# MCU.net
KiCad netlist of a schematic drawn in Altium Designer
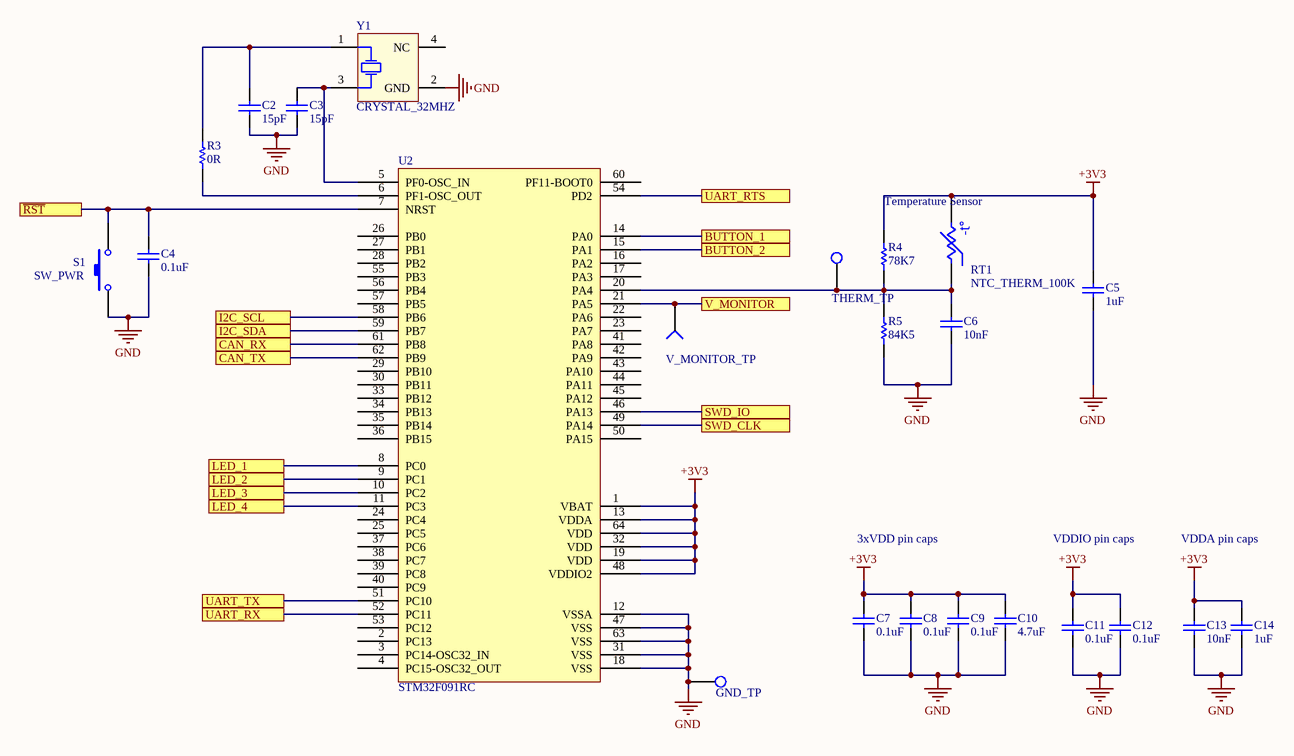
[diagram p0: MCU.SchDoc]

(export (version "E")
  (design (tool "Eeschema 10.0.6"))
  (components
    (comp (ref "C2")
      (value "15pF")
      (footprint "CAPC0603(1608)55_N")
      (description "CAP CER 15PF 250V NPO 0603")
      (fields (field (name "PART NUMBER") "AC0603JRNPOYBN150") (field (name "MANUFACTURER") "Yageo"))
      (libsource (lib "UWRT_Schematic_Library_2019") (part "CAP_15pF_0603"))
    )
    (comp (ref "C3")
      (value "15pF")
      (footprint "CAPC0603(1608)55_N")
      (description "CAP CER 15PF 250V NPO 0603")
      (fields (field (name "PART NUMBER") "AC0603JRNPOYBN150") (field (name "MANUFACTURER") "Yageo"))
      (libsource (lib "UWRT_Schematic_Library_2019") (part "CAP_15pF_0603"))
    )
    (comp (ref "C4")
      (value "0.1uF")
      (footprint "CAPC0603(1608)55_N")
      (description "CAP CER 0.1UF 16V X7R 0603")
      (fields (field (name "PART NUMBER") "CC0603KRX7R7BB104") (field (name "MANUFACTURER") "Yageo"))
      (libsource (lib "UWRT_Schematic_Library_2019") (part "CAP_0.1uF_16V_0603"))
    )
    (comp (ref "C5")
      (value "1uF")
      (footprint "CAPC0603(1608)55_N")
      (description "CAP CER 1UF 16V Y5V 0603")
      (fields (field (name "PART NUMBER") "CC0603ZRY5V7BB105") (field (name "MANUFACTURER") "Yageo"))
      (libsource (lib "UWRT_Schematic_Library_2019") (part "CAP_1uF_16V_0603"))
    )
    (comp (ref "C6")
      (value "10nF")
      (footprint "CAPC0603(1608)55_N")
      (description "CAP CER 10000PF 16V X7R 0603")
      (fields (field (name "PART NUMBER") "CC0603KRX7R7BB103") (field (name "MANUFACTURER") "Yageo"))
      (libsource (lib "UWRT_Schematic_Library_2019") (part "CAP_10nF_0603"))
    )
    (comp (ref "C7")
      (value "0.1uF")
      (footprint "CAPC0603(1608)55_N")
      (description "CAP CER 0.1UF 16V X7R 0603")
      (fields (field (name "PART NUMBER") "CC0603KRX7R7BB104") (field (name "MANUFACTURER") "Yageo"))
      (libsource (lib "UWRT_Schematic_Library_2019") (part "CAP_0.1uF_16V_0603"))
    )
    (comp (ref "C8")
      (value "0.1uF")
      (footprint "CAPC0603(1608)55_N")
      (description "CAP CER 0.1UF 16V X7R 0603")
      (fields (field (name "PART NUMBER") "CC0603KRX7R7BB104") (field (name "MANUFACTURER") "Yageo"))
      (libsource (lib "UWRT_Schematic_Library_2019") (part "CAP_0.1uF_16V_0603"))
    )
    (comp (ref "C9")
      (value "0.1uF")
      (footprint "CAPC0603(1608)55_N")
      (description "CAP CER 0.1UF 16V X7R 0603")
      (fields (field (name "PART NUMBER") "CC0603KRX7R7BB104") (field (name "MANUFACTURER") "Yageo"))
      (libsource (lib "UWRT_Schematic_Library_2019") (part "CAP_0.1uF_16V_0603"))
    )
    (comp (ref "C10")
      (value "4.7uF")
      (footprint "CAPC0603(1608)55_N")
      (description "CAP CER 4.7UF 6.3V X5R 0603")
      (fields (field (name "PART NUMBER") "CC0603KRX5R5BB475") (field (name "MANUFACTURER") "Yageo"))
      (libsource (lib "UWRT_Schematic_Library_2019") (part "CAP_4.7uF_0603"))
    )
    (comp (ref "C11")
      (value "0.1uF")
      (footprint "CAPC0603(1608)55_N")
      (description "CAP CER 0.1UF 16V X7R 0603")
      (fields (field (name "PART NUMBER") "CC0603KRX7R7BB104") (field (name "MANUFACTURER") "Yageo"))
      (libsource (lib "UWRT_Schematic_Library_2019") (part "CAP_0.1uF_16V_0603"))
    )
    (comp (ref "C12")
      (value "0.1uF")
      (footprint "CAPC0603(1608)55_N")
      (description "CAP CER 0.1UF 16V X7R 0603")
      (fields (field (name "PART NUMBER") "CC0603KRX7R7BB104") (field (name "MANUFACTURER") "Yageo"))
      (libsource (lib "UWRT_Schematic_Library_2019") (part "CAP_0.1uF_16V_0603"))
    )
    (comp (ref "C13")
      (value "10nF")
      (footprint "CAPC0603(1608)55_N")
      (description "CAP CER 10000PF 16V X7R 0603")
      (fields (field (name "PART NUMBER") "CC0603KRX7R7BB103") (field (name "MANUFACTURER") "Yageo"))
      (libsource (lib "UWRT_Schematic_Library_2019") (part "CAP_10nF_0603"))
    )
    (comp (ref "C14")
      (value "1uF")
      (footprint "CAPC0603(1608)55_N")
      (description "CAP CER 1UF 16V Y5V 0603")
      (fields (field (name "PART NUMBER") "CC0603ZRY5V7BB105") (field (name "MANUFACTURER") "Yageo"))
      (libsource (lib "UWRT_Schematic_Library_2019") (part "CAP_1uF_16V_0603"))
    )
    (comp (ref "R3")
      (value "0R")
      (footprint "RESC0603(1608)_N")
      (description "RES SMD 0 OHM JUMPER 1/10W 0603")
      (fields (field (name "MANUFACTURER") "Yageo") (field (name "Comment") "RES_0R_0603"))
      (libsource (lib "UWRT_Schematic_Library_2019") (part "RES_0R_0603"))
    )
    (comp (ref "R4")
      (value "78K7")
      (footprint "RESC0603(1608)_N")
      (description "RES SMD 78.7K OHM 1% 1/10W 0603")
      (fields (field (name "MANUFACTURER") "Yageo") (field (name "TOLERANCE") "1%"))
      (libsource (lib "UWRT_Schematic_Library_2019") (part "RES_78K7_0603"))
    )
    (comp (ref "R5")
      (value "84K5")
      (footprint "RESC0603(1608)_N")
      (description "RES SMD 84.5K OHM 1% 1/10W 0603")
      (fields (field (name "MANUFACTURER") "Yageo") (field (name "TOLERANCE") "1%"))
      (libsource (lib "UWRT_Schematic_Library_2019") (part "RES_84K5_0603"))
    )
    (comp (ref "RT1")
      (value "NTC_THERM_100K")
      (footprint "RESC0603(1608)_N")
      (description "THERM NTC 100KOHM 4700K 0603")
      (fields (field (name "MPN") "ERT-J1VV104J") (field (name "DIGIKEY PART NUMBER") "P10555CT-ND"))
      (libsource (lib "UWRT_Schematic_Library_2019") (part "NTC_THERM_100K"))
    )
    (comp (ref "S1")
      (value "SW_PWR")
      (footprint "PTS830GM140")
      (description "Power Switch (Red)")
      (fields (field (name "PART NUMBER") "PTS830GM140 SMTR LFS"))
      (libsource (lib "UWRT_Schematic_Library_2019") (part "SW_PWR"))
    )
    (comp (ref "TP3")
      (value "THERM_TP")
      (footprint "TESTPOINT_LOOP")
      (libsource (lib "UWRT_Schematic_Library_2019") (part "TESTPOINT_LOOP"))
    )
    (comp (ref "TP4")
      (value "V_MONITOR_TP")
      (footprint "TESTPOINT")
      (libsource (lib "UWRT_Schematic_Library_2019") (part "TESTPOINT_SMD"))
    )
    (comp (ref "TP5")
      (value "GND_TP")
      (footprint "TESTPOINT_LOOP")
      (libsource (lib "UWRT_Schematic_Library_2019") (part "TESTPOINT_LOOP"))
    )
    (comp (ref "U2")
      (value "STM32F091RC")
      (footprint "UWRT_Footprint_Library_2019:STM_LQFP64_N")
      (fields (field (name "MANUFACTURER") "STMicroelectronics"))
      (libsource (lib "UWRT_Schematic_Library_2019") (part "STM32F091RC"))
    )
    (comp (ref "Y1")
      (value "CRYSTAL_32MHZ")
      (footprint "AVX-CX2520DB32000D0GEJZ1-4_V")
      (description "CRYSTAL 32MHZ 8PF SMD")
      (fields
        (field (name "PART NUMBER") "CX2520DB32000D0GPSC1")
        (field (name "MANUFACTURER") "Kyocera International Inc. Electronic Components")
      )
      (libsource (lib "UWRT_Schematic_Library_2019") (part "CRYSTAL_32MHZ"))
    )
  )
  (nets
    (net (code "1") (name "+3V3") (class "Default")
      (node (ref "C10") (pin "2") (pinfunction "2_2") (pintype "passive"))
      (node (ref "C11") (pin "2") (pinfunction "2_2") (pintype "passive"))
      (node (ref "C12") (pin "2") (pinfunction "2_2") (pintype "passive"))
      (node (ref "C13") (pin "2") (pinfunction "2_2") (pintype "passive"))
      (node (ref "C14") (pin "2") (pinfunction "2_2") (pintype "passive"))
      (node (ref "C5") (pin "2") (pinfunction "2_2") (pintype "passive"))
      (node (ref "C7") (pin "2") (pinfunction "2_2") (pintype "passive"))
      (node (ref "C8") (pin "2") (pinfunction "2_2") (pintype "passive"))
      (node (ref "C9") (pin "2") (pinfunction "2_2") (pintype "passive"))
      (node (ref "R4") (pin "2") (pinfunction "2_2") (pintype "passive"))
      (node (ref "RT1") (pin "1") (pinfunction "1_1") (pintype "passive"))
      (node (ref "U2") (pin "1") (pinfunction "VBAT_1") (pintype "passive"))
      (node (ref "U2") (pin "13") (pinfunction "VDDA_13") (pintype "passive"))
      (node (ref "U2") (pin "19") (pinfunction "VDD_19") (pintype "passive"))
      (node (ref "U2") (pin "32") (pinfunction "VDD_32") (pintype "passive"))
      (node (ref "U2") (pin "48") (pinfunction "VDDIO2_48") (pintype "passive"))
      (node (ref "U2") (pin "64") (pinfunction "VDD_64") (pintype "passive"))
    )
    (net (code "2") (name "/BUTTON_1") (class "Default")
      (node (ref "U2") (pin "14") (pinfunction "PA0_14") (pintype "passive"))
    )
    (net (code "3") (name "/BUTTON_2") (class "Default")
      (node (ref "U2") (pin "15") (pinfunction "PA1_15") (pintype "passive"))
    )
    (net (code "4") (name "/CAN_RX") (class "Default")
      (node (ref "U2") (pin "61") (pinfunction "PB8_61") (pintype "passive"))
    )
    (net (code "5") (name "/CAN_TX") (class "Default")
      (node (ref "U2") (pin "62") (pinfunction "PB9_62") (pintype "passive"))
    )
    (net (code "6") (name "/I2C_SCL") (class "Default")
      (node (ref "U2") (pin "58") (pinfunction "PB6_58") (pintype "passive"))
    )
    (net (code "7") (name "/I2C_SDA") (class "Default")
      (node (ref "U2") (pin "59") (pinfunction "PB7_59") (pintype "passive"))
    )
    (net (code "8") (name "/LED_1") (class "Default")
      (node (ref "U2") (pin "8") (pinfunction "PC0_8") (pintype "passive"))
    )
    (net (code "9") (name "/LED_2") (class "Default")
      (node (ref "U2") (pin "9") (pinfunction "PC1_9") (pintype "passive"))
    )
    (net (code "10") (name "/LED_3") (class "Default")
      (node (ref "U2") (pin "10") (pinfunction "PC2_10") (pintype "passive"))
    )
    (net (code "11") (name "/LED_4") (class "Default")
      (node (ref "U2") (pin "11") (pinfunction "PC3_11") (pintype "passive"))
    )
    (net (code "12") (name "/SWD_CLK") (class "Default")
      (node (ref "U2") (pin "49") (pinfunction "PA14_49") (pintype "passive"))
    )
    (net (code "13") (name "/SWD_IO") (class "Default")
      (node (ref "U2") (pin "46") (pinfunction "PA13_46") (pintype "passive"))
    )
    (net (code "14") (name "/UART_RTS") (class "Default")
      (node (ref "U2") (pin "54") (pinfunction "PD2_54") (pintype "passive"))
    )
    (net (code "15") (name "/UART_RX") (class "Default")
      (node (ref "U2") (pin "52") (pinfunction "PC11_52") (pintype "passive"))
    )
    (net (code "16") (name "/UART_TX") (class "Default")
      (node (ref "U2") (pin "51") (pinfunction "PC10_51") (pintype "passive"))
    )
    (net (code "17") (name "/V_MONITOR") (class "Default")
      (node (ref "TP4") (pin "1") (pinfunction "=value_1") (pintype "passive"))
      (node (ref "U2") (pin "21") (pinfunction "PA5_21") (pintype "passive"))
    )
    (net (code "18") (name "/~{RST}") (class "Default")
      (node (ref "C4") (pin "2") (pinfunction "2_2") (pintype "passive"))
      (node (ref "S1") (pin "2") (pinfunction "2_2") (pintype "passive"))
      (node (ref "U2") (pin "7") (pinfunction "NRST_7") (pintype "passive"))
    )
    (net (code "19") (name "GND") (class "Default")
      (node (ref "C10") (pin "1") (pinfunction "1_1") (pintype "passive"))
      (node (ref "C11") (pin "1") (pinfunction "1_1") (pintype "passive"))
      (node (ref "C12") (pin "1") (pinfunction "1_1") (pintype "passive"))
      (node (ref "C13") (pin "1") (pinfunction "1_1") (pintype "passive"))
      (node (ref "C14") (pin "1") (pinfunction "1_1") (pintype "passive"))
      (node (ref "C2") (pin "1") (pinfunction "1_1") (pintype "passive"))
      (node (ref "C3") (pin "1") (pinfunction "1_1") (pintype "passive"))
      (node (ref "C4") (pin "1") (pinfunction "1_1") (pintype "passive"))
      (node (ref "C5") (pin "1") (pinfunction "1_1") (pintype "passive"))
      (node (ref "C6") (pin "1") (pinfunction "1_1") (pintype "passive"))
      (node (ref "C7") (pin "1") (pinfunction "1_1") (pintype "passive"))
      (node (ref "C8") (pin "1") (pinfunction "1_1") (pintype "passive"))
      (node (ref "C9") (pin "1") (pinfunction "1_1") (pintype "passive"))
      (node (ref "R5") (pin "1") (pinfunction "1_1") (pintype "passive"))
      (node (ref "S1") (pin "1") (pinfunction "1_1") (pintype "passive"))
      (node (ref "TP5") (pin "1") (pinfunction "=value_1") (pintype "passive"))
      (node (ref "U2") (pin "12") (pinfunction "VSSA_12") (pintype "passive"))
      (node (ref "U2") (pin "18") (pinfunction "VSS_18") (pintype "passive"))
      (node (ref "U2") (pin "31") (pinfunction "VSS_31") (pintype "passive"))
      (node (ref "U2") (pin "47") (pinfunction "VSS_47") (pintype "passive"))
      (node (ref "U2") (pin "63") (pinfunction "VSS_63") (pintype "passive"))
      (node (ref "Y1") (pin "2") (pinfunction "GND_2") (pintype "power_in"))
    )
    (net (code "20") (name "Net-(C2-Pad2)") (class "Default")
      (node (ref "C2") (pin "2") (pinfunction "2_2") (pintype "passive"))
      (node (ref "R3") (pin "2") (pinfunction "2_2") (pintype "passive"))
      (node (ref "Y1") (pin "1") (pinfunction "HOT_1") (pintype "passive"))
    )
    (net (code "21") (name "Net-(TP3-=value)") (class "Default")
      (node (ref "C6") (pin "2") (pinfunction "2_2") (pintype "passive"))
      (node (ref "R4") (pin "1") (pinfunction "1_1") (pintype "passive"))
      (node (ref "R5") (pin "2") (pinfunction "2_2") (pintype "passive"))
      (node (ref "RT1") (pin "2") (pinfunction "2_2") (pintype "passive"))
      (node (ref "TP3") (pin "1") (pinfunction "=value_1") (pintype "passive"))
      (node (ref "U2") (pin "20") (pinfunction "PA4_20") (pintype "passive"))
    )
    (net (code "22") (name "Net-(U2-PF0-OSC_IN)") (class "Default")
      (node (ref "C3") (pin "2") (pinfunction "2_2") (pintype "passive"))
      (node (ref "U2") (pin "5") (pinfunction "PF0-OSC_IN_5") (pintype "passive"))
      (node (ref "Y1") (pin "3") (pinfunction "HOT_3") (pintype "passive"))
    )
    (net (code "23") (name "Net-(U2-PF1-OSC_OUT)") (class "Default")
      (node (ref "R3") (pin "1") (pinfunction "1_1") (pintype "passive"))
      (node (ref "U2") (pin "6") (pinfunction "PF1-OSC_OUT_6") (pintype "passive"))
    )
    (net (code "24") (name "unconnected-(U2-PA2-Pad16)") (class "Default")
      (node (ref "U2") (pin "16") (pinfunction "PA2_16") (pintype "passive"))
    )
    (net (code "25") (name "unconnected-(U2-PA3-Pad17)") (class "Default")
      (node (ref "U2") (pin "17") (pinfunction "PA3_17") (pintype "passive"))
    )
    (net (code "26") (name "unconnected-(U2-PA6-Pad22)") (class "Default")
      (node (ref "U2") (pin "22") (pinfunction "PA6_22") (pintype "passive"))
    )
    (net (code "27") (name "unconnected-(U2-PA7-Pad23)") (class "Default")
      (node (ref "U2") (pin "23") (pinfunction "PA7_23") (pintype "passive"))
    )
    (net (code "28") (name "unconnected-(U2-PA8-Pad41)") (class "Default")
      (node (ref "U2") (pin "41") (pinfunction "PA8_41") (pintype "passive"))
    )
    (net (code "29") (name "unconnected-(U2-PA9-Pad42)") (class "Default")
      (node (ref "U2") (pin "42") (pinfunction "PA9_42") (pintype "passive"))
    )
    (net (code "30") (name "unconnected-(U2-PA10-Pad43)") (class "Default")
      (node (ref "U2") (pin "43") (pinfunction "PA10_43") (pintype "passive"))
    )
    (net (code "31") (name "unconnected-(U2-PA11-Pad44)") (class "Default")
      (node (ref "U2") (pin "44") (pinfunction "PA11_44") (pintype "passive"))
    )
    (net (code "32") (name "unconnected-(U2-PA12-Pad45)") (class "Default")
      (node (ref "U2") (pin "45") (pinfunction "PA12_45") (pintype "passive"))
    )
    (net (code "33") (name "unconnected-(U2-PA15-Pad50)") (class "Default")
      (node (ref "U2") (pin "50") (pinfunction "PA15_50") (pintype "passive"))
    )
    (net (code "34") (name "unconnected-(U2-PB0-Pad26)") (class "Default")
      (node (ref "U2") (pin "26") (pinfunction "PB0_26") (pintype "passive"))
    )
    (net (code "35") (name "unconnected-(U2-PB1-Pad27)") (class "Default")
      (node (ref "U2") (pin "27") (pinfunction "PB1_27") (pintype "passive"))
    )
    (net (code "36") (name "unconnected-(U2-PB2-Pad28)") (class "Default")
      (node (ref "U2") (pin "28") (pinfunction "PB2_28") (pintype "passive"))
    )
    (net (code "37") (name "unconnected-(U2-PB3-Pad55)") (class "Default")
      (node (ref "U2") (pin "55") (pinfunction "PB3_55") (pintype "passive"))
    )
    (net (code "38") (name "unconnected-(U2-PB4-Pad56)") (class "Default")
      (node (ref "U2") (pin "56") (pinfunction "PB4_56") (pintype "passive"))
    )
    (net (code "39") (name "unconnected-(U2-PB5-Pad57)") (class "Default")
      (node (ref "U2") (pin "57") (pinfunction "PB5_57") (pintype "passive"))
    )
    (net (code "40") (name "unconnected-(U2-PB10-Pad29)") (class "Default")
      (node (ref "U2") (pin "29") (pinfunction "PB10_29") (pintype "passive"))
    )
    (net (code "41") (name "unconnected-(U2-PB11-Pad30)") (class "Default")
      (node (ref "U2") (pin "30") (pinfunction "PB11_30") (pintype "passive"))
    )
    (net (code "42") (name "unconnected-(U2-PB12-Pad33)") (class "Default")
      (node (ref "U2") (pin "33") (pinfunction "PB12_33") (pintype "passive"))
    )
    (net (code "43") (name "unconnected-(U2-PB13-Pad34)") (class "Default")
      (node (ref "U2") (pin "34") (pinfunction "PB13_34") (pintype "passive"))
    )
    (net (code "44") (name "unconnected-(U2-PB14-Pad35)") (class "Default")
      (node (ref "U2") (pin "35") (pinfunction "PB14_35") (pintype "passive"))
    )
    (net (code "45") (name "unconnected-(U2-PB15-Pad36)") (class "Default")
      (node (ref "U2") (pin "36") (pinfunction "PB15_36") (pintype "passive"))
    )
    (net (code "46") (name "unconnected-(U2-PC4-Pad24)") (class "Default")
      (node (ref "U2") (pin "24") (pinfunction "PC4_24") (pintype "passive"))
    )
    (net (code "47") (name "unconnected-(U2-PC5-Pad25)") (class "Default")
      (node (ref "U2") (pin "25") (pinfunction "PC5_25") (pintype "passive"))
    )
    (net (code "48") (name "unconnected-(U2-PC6-Pad37)") (class "Default")
      (node (ref "U2") (pin "37") (pinfunction "PC6_37") (pintype "passive"))
    )
    (net (code "49") (name "unconnected-(U2-PC7-Pad38)") (class "Default")
      (node (ref "U2") (pin "38") (pinfunction "PC7_38") (pintype "passive"))
    )
    (net (code "50") (name "unconnected-(U2-PC8-Pad39)") (class "Default")
      (node (ref "U2") (pin "39") (pinfunction "PC8_39") (pintype "passive"))
    )
    (net (code "51") (name "unconnected-(U2-PC9-Pad40)") (class "Default")
      (node (ref "U2") (pin "40") (pinfunction "PC9_40") (pintype "passive"))
    )
    (net (code "52") (name "unconnected-(U2-PC12-Pad53)") (class "Default")
      (node (ref "U2") (pin "53") (pinfunction "PC12_53") (pintype "passive"))
    )
    (net (code "53") (name "unconnected-(U2-PC13-Pad2)") (class "Default")
      (node (ref "U2") (pin "2") (pinfunction "PC13_2") (pintype "passive"))
    )
    (net (code "54") (name "unconnected-(U2-PC14-OSC32_IN-Pad3)") (class "Default")
      (node (ref "U2") (pin "3") (pinfunction "PC14-OSC32_IN_3") (pintype "passive"))
    )
    (net (code "55") (name "unconnected-(U2-PC15-OSC32_OUT-Pad4)") (class "Default")
      (node (ref "U2") (pin "4") (pinfunction "PC15-OSC32_OUT_4") (pintype "passive"))
    )
    (net (code "56") (name "unconnected-(U2-PF11-BOOT0-Pad60)") (class "Default")
      (node (ref "U2") (pin "60") (pinfunction "PF11-BOOT0_60") (pintype "passive"))
    )
    (net (code "57") (name "unconnected-(Y1-NC-Pad4)") (class "Default")
      (node (ref "Y1") (pin "4") (pinfunction "NC_4") (pintype "passive"))
    )
  )
)
